# iLight.net
KiCad netlist of a schematic drawn in EAGLE
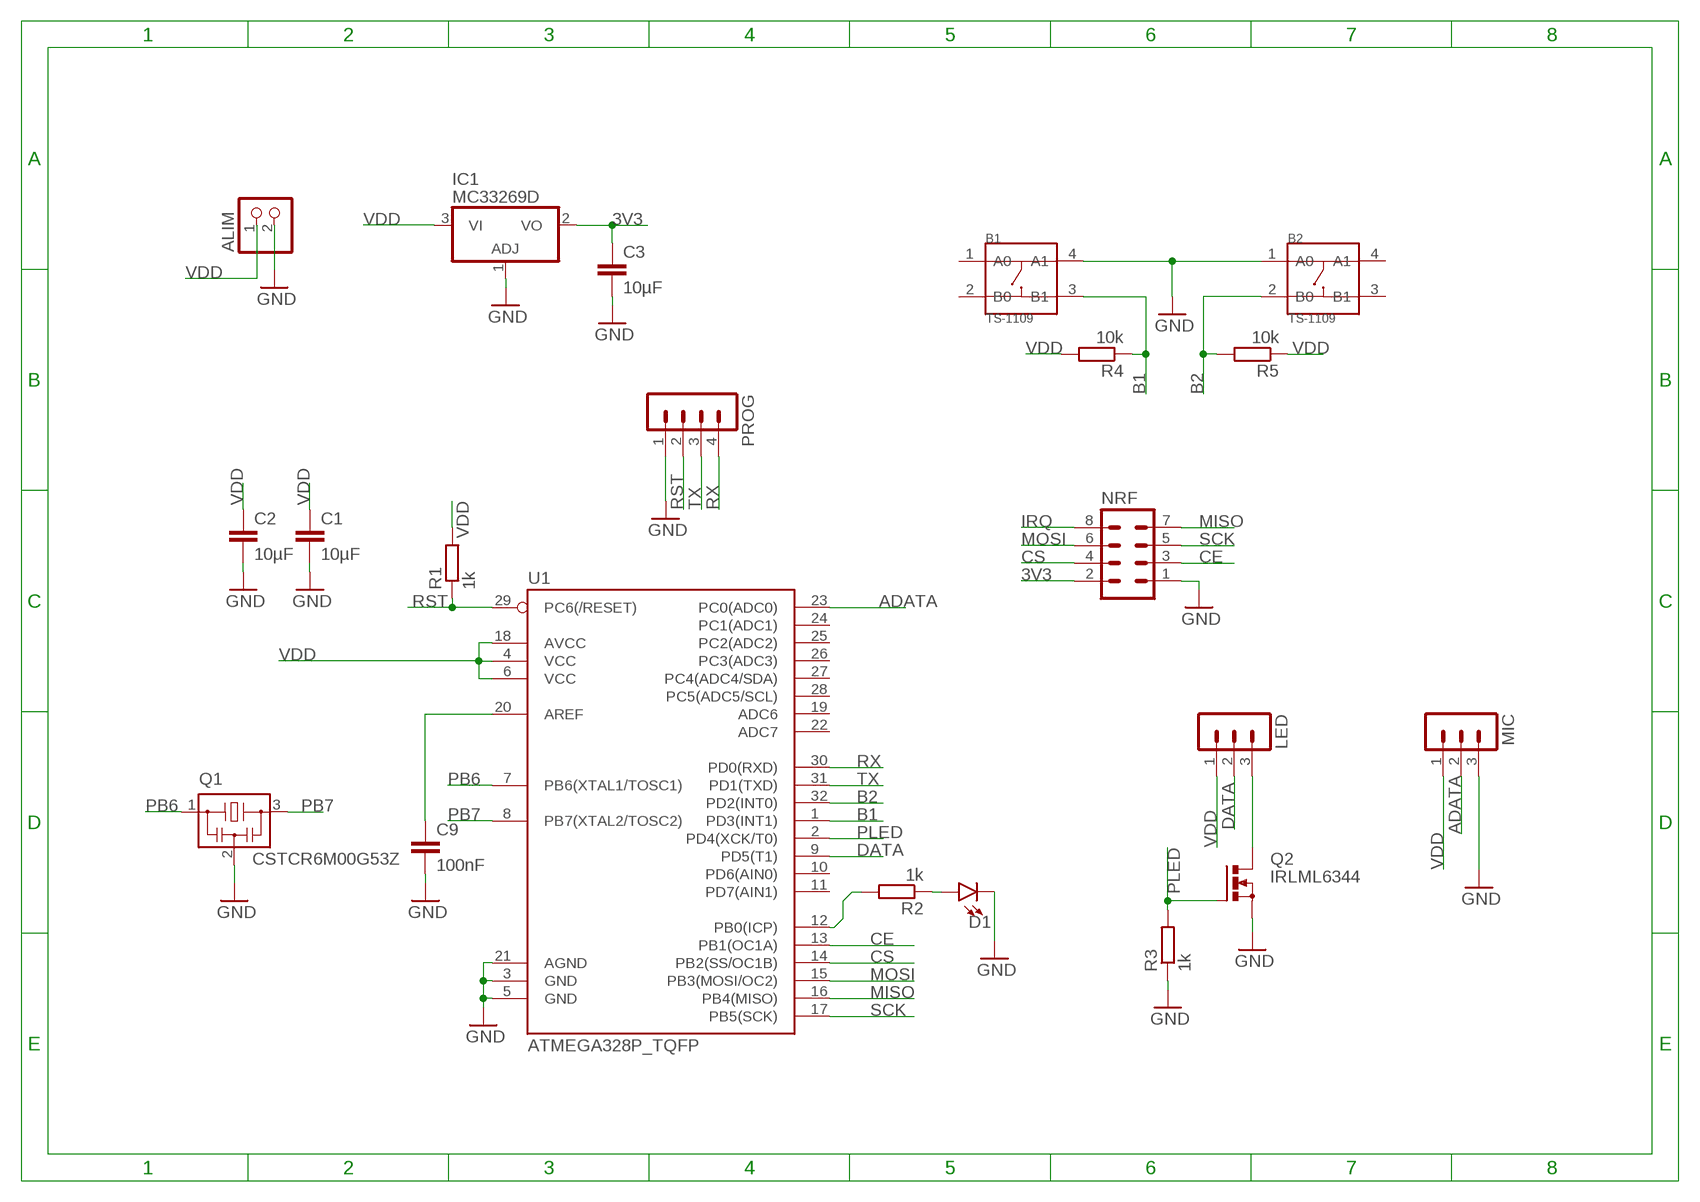
[diagram p0: schematic, sheet 1]

(export (version "E")
  (design (tool "Eeschema 10.0.6"))
  (components
    (comp (ref "ALIM")
      (value "PINHD-1X2")
      (footprint "eagle-import:1X02")
      (libsource (lib "eagle-import") (part "PINHD-1X2"))
    )
    (comp (ref "B1")
      (value "TS-1109")
      (footprint "eagle-import:SW4-6.0X6.0X5.0MM")
      (libsource (lib "eagle-import") (part "DIP-BUTTON-4P"))
    )
    (comp (ref "B2")
      (value "TS-1109")
      (footprint "eagle-import:SW4-6.0X6.0X5.0MM")
      (libsource (lib "eagle-import") (part "DIP-BUTTON-4P"))
    )
    (comp (ref "C1")
      (value "10µF")
      (footprint "eagle-import:C1206")
      (libsource (lib "eagle-import") (part "C-EUC1206"))
    )
    (comp (ref "C2")
      (value "10µF")
      (footprint "eagle-import:C1206")
      (libsource (lib "eagle-import") (part "C-EUC1206"))
    )
    (comp (ref "C3")
      (value "10µF")
      (footprint "eagle-import:C1206")
      (libsource (lib "eagle-import") (part "C-EUC1206"))
    )
    (comp (ref "C9")
      (value "100nF")
      (footprint "eagle-import:C1206")
      (libsource (lib "eagle-import") (part "C-EUC1206"))
    )
    (comp (ref "D1")
      (value "LED-FKIT-1206")
      (footprint "eagle-import:FKIT-LED-1206")
      (libsource (lib "eagle-import") (part "LED-FKIT-1206"))
    )
    (comp (ref "IC1")
      (value "MC33269D")
      (footprint "eagle-import:DPACK")
      (libsource (lib "eagle-import") (part "MC33269?D"))
    )
    (comp (ref "LED")
      (value "MA03-1")
      (footprint "eagle-import:MA03-1")
      (libsource (lib "eagle-import") (part "MA03-1"))
    )
    (comp (ref "MIC")
      (value "MA03-1")
      (footprint "eagle-import:MA03-1")
      (libsource (lib "eagle-import") (part "MA03-1"))
    )
    (comp (ref "NRF")
      (value "MA04-2")
      (footprint "eagle-import:MA04-2")
      (libsource (lib "eagle-import") (part "MA04-2"))
    )
    (comp (ref "PROG")
      (value "MA04-1")
      (footprint "eagle-import:MA04-1")
      (libsource (lib "eagle-import") (part "MA04-1"))
    )
    (comp (ref "Q1")
      (value "CSTCR6M00G53Z")
      (footprint "eagle-import:CSTCR6M")
      (fields (field (name "MPN") "CSTCR6M00G53-R0"))
      (libsource (lib "eagle-import") (part "CSTCR6M00G53Z"))
    )
    (comp (ref "Q2")
      (value "IRLML6344")
      (footprint "eagle-import:SOT-23")
      (libsource (lib "eagle-import") (part "IRLML6344"))
    )
    (comp (ref "R1")
      (value "1k")
      (footprint "eagle-import:R1206")
      (libsource (lib "eagle-import") (part "R-EU_R1206"))
    )
    (comp (ref "R2")
      (value "1k")
      (footprint "eagle-import:R1206")
      (libsource (lib "eagle-import") (part "R-EU_R1206"))
    )
    (comp (ref "R3")
      (value "1k")
      (footprint "eagle-import:R1206")
      (libsource (lib "eagle-import") (part "R-EU_R1206"))
    )
    (comp (ref "R4")
      (value "10k")
      (footprint "eagle-import:R1206")
      (libsource (lib "eagle-import") (part "R-EU_R1206"))
    )
    (comp (ref "R5")
      (value "10k")
      (footprint "eagle-import:R1206")
      (libsource (lib "eagle-import") (part "R-EU_R1206"))
    )
    (comp (ref "U1")
      (value "ATMEGA328P_TQFP")
      (footprint "eagle-import:TQFP32-08")
      (libsource (lib "eagle-import") (part "ATMEGA328P_TQFP"))
    )
  )
  (nets
    (net (code "1") (name "/3V3") (class "Default")
      (node (ref "C3") (pin "1") (pinfunction "1_1") (pintype "passive"))
      (node (ref "IC1") (pin "2") (pinfunction "VO_2") (pintype "passive"))
      (node (ref "NRF") (pin "2") (pinfunction "2_2") (pintype "passive"))
    )
    (net (code "2") (name "/ADATA") (class "Default")
      (node (ref "MIC") (pin "2") (pinfunction "2_2") (pintype "passive"))
      (node (ref "U1") (pin "23") (pinfunction "PC0(ADC0)_23") (pintype "bidirectional"))
    )
    (net (code "3") (name "/B1") (class "Default")
      (node (ref "B1") (pin "3") (pinfunction "B1_3") (pintype "bidirectional"))
      (node (ref "R4") (pin "1") (pinfunction "1_1") (pintype "passive"))
      (node (ref "U1") (pin "1") (pinfunction "PD3(INT1)_1") (pintype "bidirectional"))
    )
    (net (code "4") (name "/B2") (class "Default")
      (node (ref "B2") (pin "2") (pinfunction "B0_2") (pintype "bidirectional"))
      (node (ref "R5") (pin "2") (pinfunction "2_2") (pintype "passive"))
      (node (ref "U1") (pin "32") (pinfunction "PD2(INT0)_32") (pintype "bidirectional"))
    )
    (net (code "5") (name "/CE") (class "Default")
      (node (ref "NRF") (pin "3") (pinfunction "3_3") (pintype "passive"))
      (node (ref "U1") (pin "13") (pinfunction "PB1(OC1A)_13") (pintype "bidirectional"))
    )
    (net (code "6") (name "/CS") (class "Default")
      (node (ref "NRF") (pin "4") (pinfunction "4_4") (pintype "passive"))
      (node (ref "U1") (pin "14") (pinfunction "PB2(SS/OC1B)_14") (pintype "bidirectional"))
    )
    (net (code "7") (name "/DATA") (class "Default")
      (node (ref "LED") (pin "2") (pinfunction "2_2") (pintype "passive"))
      (node (ref "U1") (pin "9") (pinfunction "PD5(T1)_9") (pintype "bidirectional"))
    )
    (net (code "8") (name "/IRQ") (class "Default")
      (node (ref "NRF") (pin "8") (pinfunction "8_8") (pintype "passive"))
    )
    (net (code "9") (name "/MISO") (class "Default")
      (node (ref "NRF") (pin "7") (pinfunction "7_7") (pintype "passive"))
      (node (ref "U1") (pin "16") (pinfunction "PB4(MISO)_16") (pintype "bidirectional"))
    )
    (net (code "10") (name "/MOSI") (class "Default")
      (node (ref "NRF") (pin "6") (pinfunction "6_6") (pintype "passive"))
      (node (ref "U1") (pin "15") (pinfunction "PB3(MOSI/OC2)_15") (pintype "bidirectional"))
    )
    (net (code "11") (name "/PB6") (class "Default")
      (node (ref "Q1") (pin "1") (pinfunction "1_1") (pintype "passive"))
      (node (ref "U1") (pin "7") (pinfunction "PB6(XTAL1/TOSC1)_7") (pintype "bidirectional"))
    )
    (net (code "12") (name "/PB7") (class "Default")
      (node (ref "Q1") (pin "3") (pinfunction "3_3") (pintype "passive"))
      (node (ref "U1") (pin "8") (pinfunction "PB7(XTAL2/TOSC2)_8") (pintype "bidirectional"))
    )
    (net (code "13") (name "/PLED") (class "Default")
      (node (ref "Q2") (pin "P1") (pinfunction "G_P1") (pintype "passive"))
      (node (ref "R3") (pin "2") (pinfunction "2_2") (pintype "passive"))
      (node (ref "U1") (pin "2") (pinfunction "PD4(XCK/T0)_2") (pintype "bidirectional"))
    )
    (net (code "14") (name "/RST") (class "Default")
      (node (ref "PROG") (pin "2") (pinfunction "2_2") (pintype "passive"))
      (node (ref "R1") (pin "1") (pinfunction "1_1") (pintype "passive"))
      (node (ref "U1") (pin "29") (pinfunction "PC6(/RESET)_29") (pintype "bidirectional"))
    )
    (net (code "15") (name "/RX") (class "Default")
      (node (ref "PROG") (pin "4") (pinfunction "4_4") (pintype "passive"))
      (node (ref "U1") (pin "30") (pinfunction "PD0(RXD)_30") (pintype "bidirectional"))
    )
    (net (code "16") (name "/SCK") (class "Default")
      (node (ref "NRF") (pin "5") (pinfunction "5_5") (pintype "passive"))
      (node (ref "U1") (pin "17") (pinfunction "PB5(SCK)_17") (pintype "bidirectional"))
    )
    (net (code "17") (name "/TX") (class "Default")
      (node (ref "PROG") (pin "3") (pinfunction "3_3") (pintype "passive"))
      (node (ref "U1") (pin "31") (pinfunction "PD1(TXD)_31") (pintype "bidirectional"))
    )
    (net (code "18") (name "/VDD") (class "Default")
      (node (ref "ALIM") (pin "1") (pinfunction "1_1") (pintype "passive"))
      (node (ref "C1") (pin "1") (pinfunction "1_1") (pintype "passive"))
      (node (ref "C2") (pin "1") (pinfunction "1_1") (pintype "passive"))
      (node (ref "IC1") (pin "3") (pinfunction "VI_3") (pintype "input"))
      (node (ref "LED") (pin "1") (pinfunction "1_1") (pintype "passive"))
      (node (ref "MIC") (pin "1") (pinfunction "1_1") (pintype "passive"))
      (node (ref "R1") (pin "2") (pinfunction "2_2") (pintype "passive"))
      (node (ref "R4") (pin "2") (pinfunction "2_2") (pintype "passive"))
      (node (ref "R5") (pin "1") (pinfunction "1_1") (pintype "passive"))
      (node (ref "U1") (pin "18") (pinfunction "AVCC_18") (pintype "bidirectional"))
      (node (ref "U1") (pin "4") (pinfunction "VCC_4") (pintype "bidirectional"))
      (node (ref "U1") (pin "6") (pinfunction "VCC_6") (pintype "bidirectional"))
    )
    (net (code "19") (name "GND") (class "Default")
      (node (ref "ALIM") (pin "2") (pinfunction "2_2") (pintype "passive"))
      (node (ref "B1") (pin "4") (pinfunction "A1_4") (pintype "bidirectional"))
      (node (ref "B2") (pin "1") (pinfunction "A0_1") (pintype "bidirectional"))
      (node (ref "C1") (pin "2") (pinfunction "2_2") (pintype "passive"))
      (node (ref "C2") (pin "2") (pinfunction "2_2") (pintype "passive"))
      (node (ref "C3") (pin "2") (pinfunction "2_2") (pintype "passive"))
      (node (ref "C9") (pin "2") (pinfunction "2_2") (pintype "passive"))
      (node (ref "D1") (pin "C") (pinfunction "C_C") (pintype "passive"))
      (node (ref "IC1") (pin "1") (pinfunction "ADJ_1") (pintype "input"))
      (node (ref "MIC") (pin "3") (pinfunction "3_3") (pintype "passive"))
      (node (ref "NRF") (pin "1") (pinfunction "1_1") (pintype "passive"))
      (node (ref "PROG") (pin "1") (pinfunction "1_1") (pintype "passive"))
      (node (ref "Q1") (pin "2") (pinfunction "2_2") (pintype "passive"))
      (node (ref "Q2") (pin "P2") (pinfunction "S_P2") (pintype "passive"))
      (node (ref "R3") (pin "1") (pinfunction "1_1") (pintype "passive"))
      (node (ref "U1") (pin "21") (pinfunction "AGND_21") (pintype "bidirectional"))
      (node (ref "U1") (pin "3") (pinfunction "GND_3") (pintype "bidirectional"))
      (node (ref "U1") (pin "5") (pinfunction "GND_5") (pintype "bidirectional"))
    )
    (net (code "20") (name "Net-(D1-PadA)") (class "Default")
      (node (ref "D1") (pin "A") (pinfunction "A_A") (pintype "passive"))
      (node (ref "R2") (pin "1") (pinfunction "1_1") (pintype "passive"))
    )
    (net (code "21") (name "Net-(Q2-D)") (class "Default")
      (node (ref "LED") (pin "3") (pinfunction "3_3") (pintype "passive"))
      (node (ref "Q2") (pin "P3") (pinfunction "D_P3") (pintype "passive"))
    )
    (net (code "22") (name "Net-(U1-AREF)") (class "Default")
      (node (ref "C9") (pin "1") (pinfunction "1_1") (pintype "passive"))
      (node (ref "U1") (pin "20") (pinfunction "AREF_20") (pintype "bidirectional"))
    )
    (net (code "23") (name "Net-(U1-PB0(ICP))") (class "Default")
      (node (ref "R2") (pin "2") (pinfunction "2_2") (pintype "passive"))
      (node (ref "U1") (pin "12") (pinfunction "PB0(ICP)_12") (pintype "bidirectional"))
    )
    (net (code "24") (name "unconnected-(B1-A0-Pad1)") (class "Default")
      (node (ref "B1") (pin "1") (pinfunction "A0_1") (pintype "bidirectional"))
    )
    (net (code "25") (name "unconnected-(B1-B0-Pad2)") (class "Default")
      (node (ref "B1") (pin "2") (pinfunction "B0_2") (pintype "bidirectional"))
    )
    (net (code "26") (name "unconnected-(B2-A1-Pad4)") (class "Default")
      (node (ref "B2") (pin "4") (pinfunction "A1_4") (pintype "bidirectional"))
    )
    (net (code "27") (name "unconnected-(B2-B1-Pad3)") (class "Default")
      (node (ref "B2") (pin "3") (pinfunction "B1_3") (pintype "bidirectional"))
    )
    (net (code "28") (name "unconnected-(U1-ADC6-Pad19)") (class "Default")
      (node (ref "U1") (pin "19") (pinfunction "ADC6_19") (pintype "bidirectional"))
    )
    (net (code "29") (name "unconnected-(U1-ADC7-Pad22)") (class "Default")
      (node (ref "U1") (pin "22") (pinfunction "ADC7_22") (pintype "bidirectional"))
    )
    (net (code "30") (name "unconnected-(U1-PC1(ADC1)-Pad24)") (class "Default")
      (node (ref "U1") (pin "24") (pinfunction "PC1(ADC1)_24") (pintype "bidirectional"))
    )
    (net (code "31") (name "unconnected-(U1-PC2(ADC2)-Pad25)") (class "Default")
      (node (ref "U1") (pin "25") (pinfunction "PC2(ADC2)_25") (pintype "bidirectional"))
    )
    (net (code "32") (name "unconnected-(U1-PC3(ADC3)-Pad26)") (class "Default")
      (node (ref "U1") (pin "26") (pinfunction "PC3(ADC3)_26") (pintype "bidirectional"))
    )
    (net (code "33") (name "unconnected-(U1-PC4(ADC4{slash}SDA)-Pad27)") (class "Default")
      (node (ref "U1") (pin "27") (pinfunction "PC4(ADC4/SDA)_27") (pintype "bidirectional"))
    )
    (net (code "34") (name "unconnected-(U1-PC5(ADC5{slash}SCL)-Pad28)") (class "Default")
      (node (ref "U1") (pin "28") (pinfunction "PC5(ADC5/SCL)_28") (pintype "bidirectional"))
    )
    (net (code "35") (name "unconnected-(U1-PD6(AIN0)-Pad10)") (class "Default")
      (node (ref "U1") (pin "10") (pinfunction "PD6(AIN0)_10") (pintype "bidirectional"))
    )
    (net (code "36") (name "unconnected-(U1-PD7(AIN1)-Pad11)") (class "Default")
      (node (ref "U1") (pin "11") (pinfunction "PD7(AIN1)_11") (pintype "bidirectional"))
    )
  )
)
